# BatteryBalancer.net
KiCad netlist of a schematic drawn in EAGLE
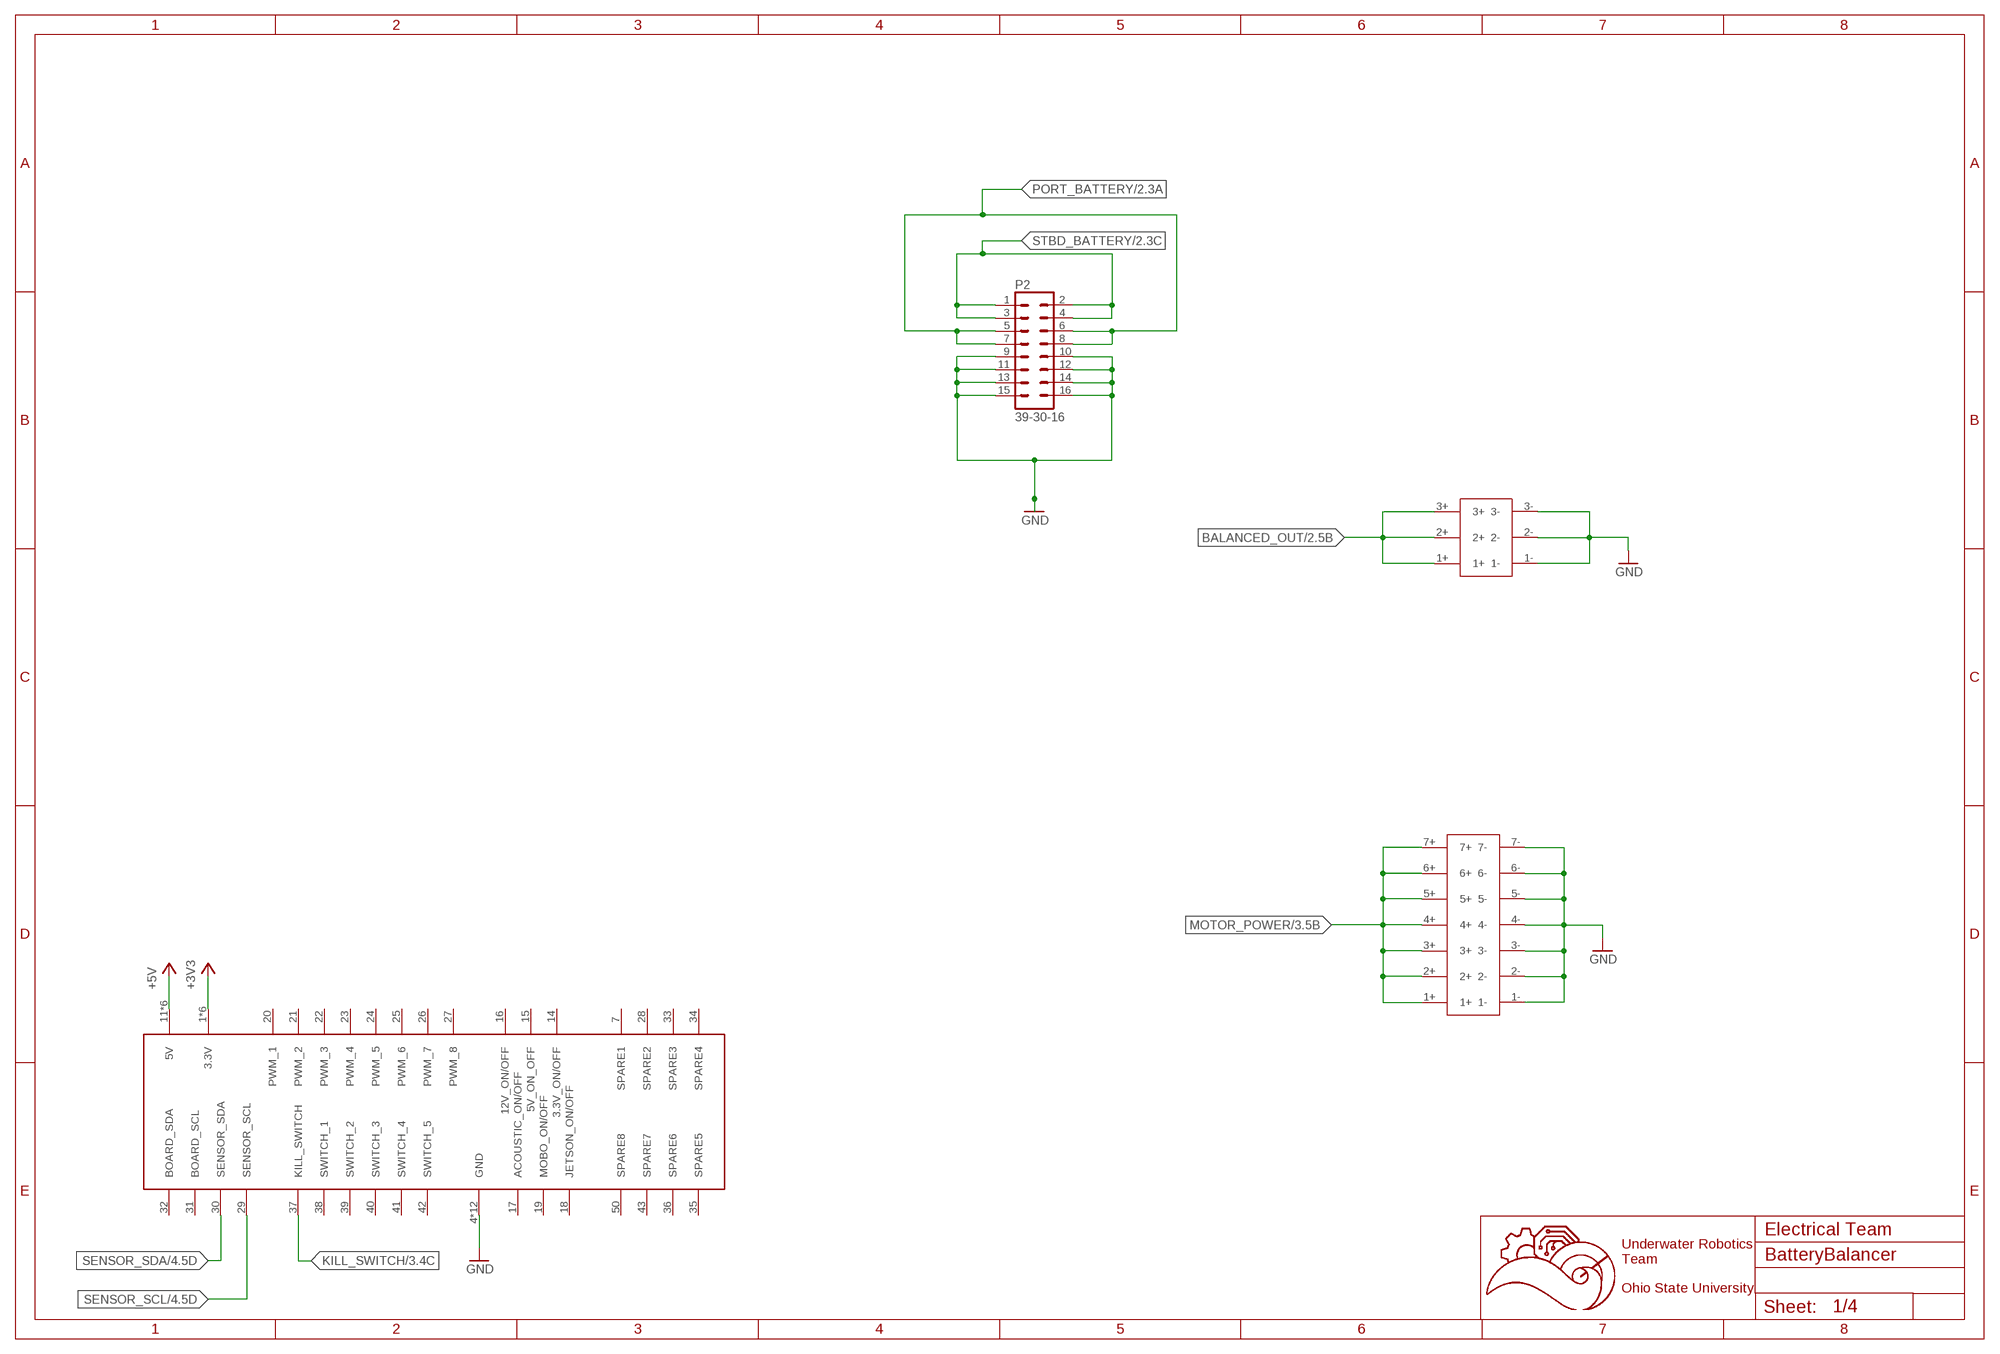
[diagram p0: schematic, sheet 1]
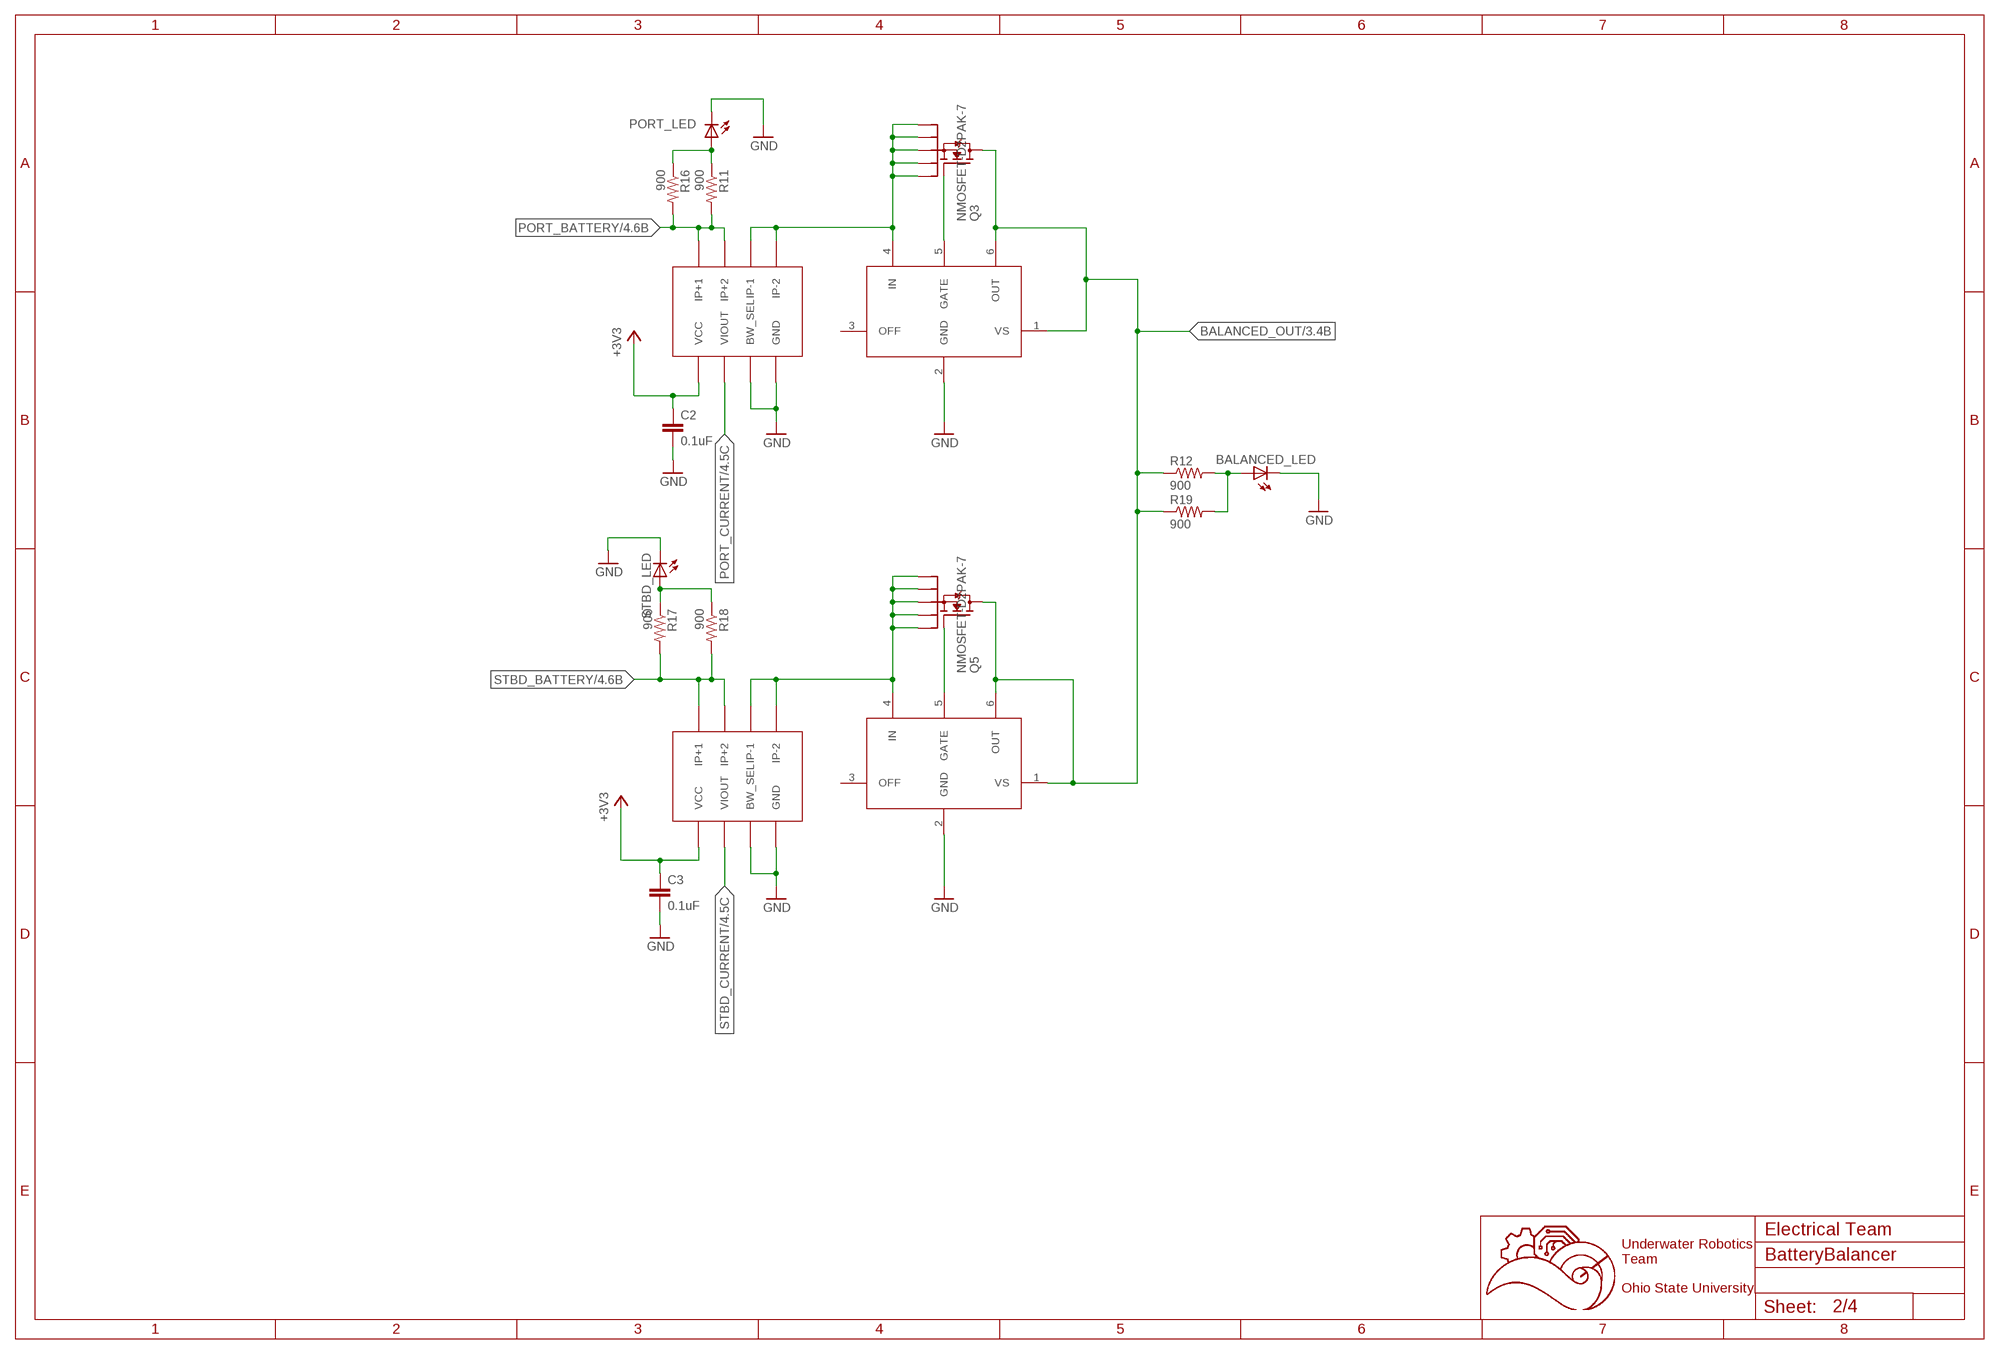
[diagram p1: schematic, sheet 2]
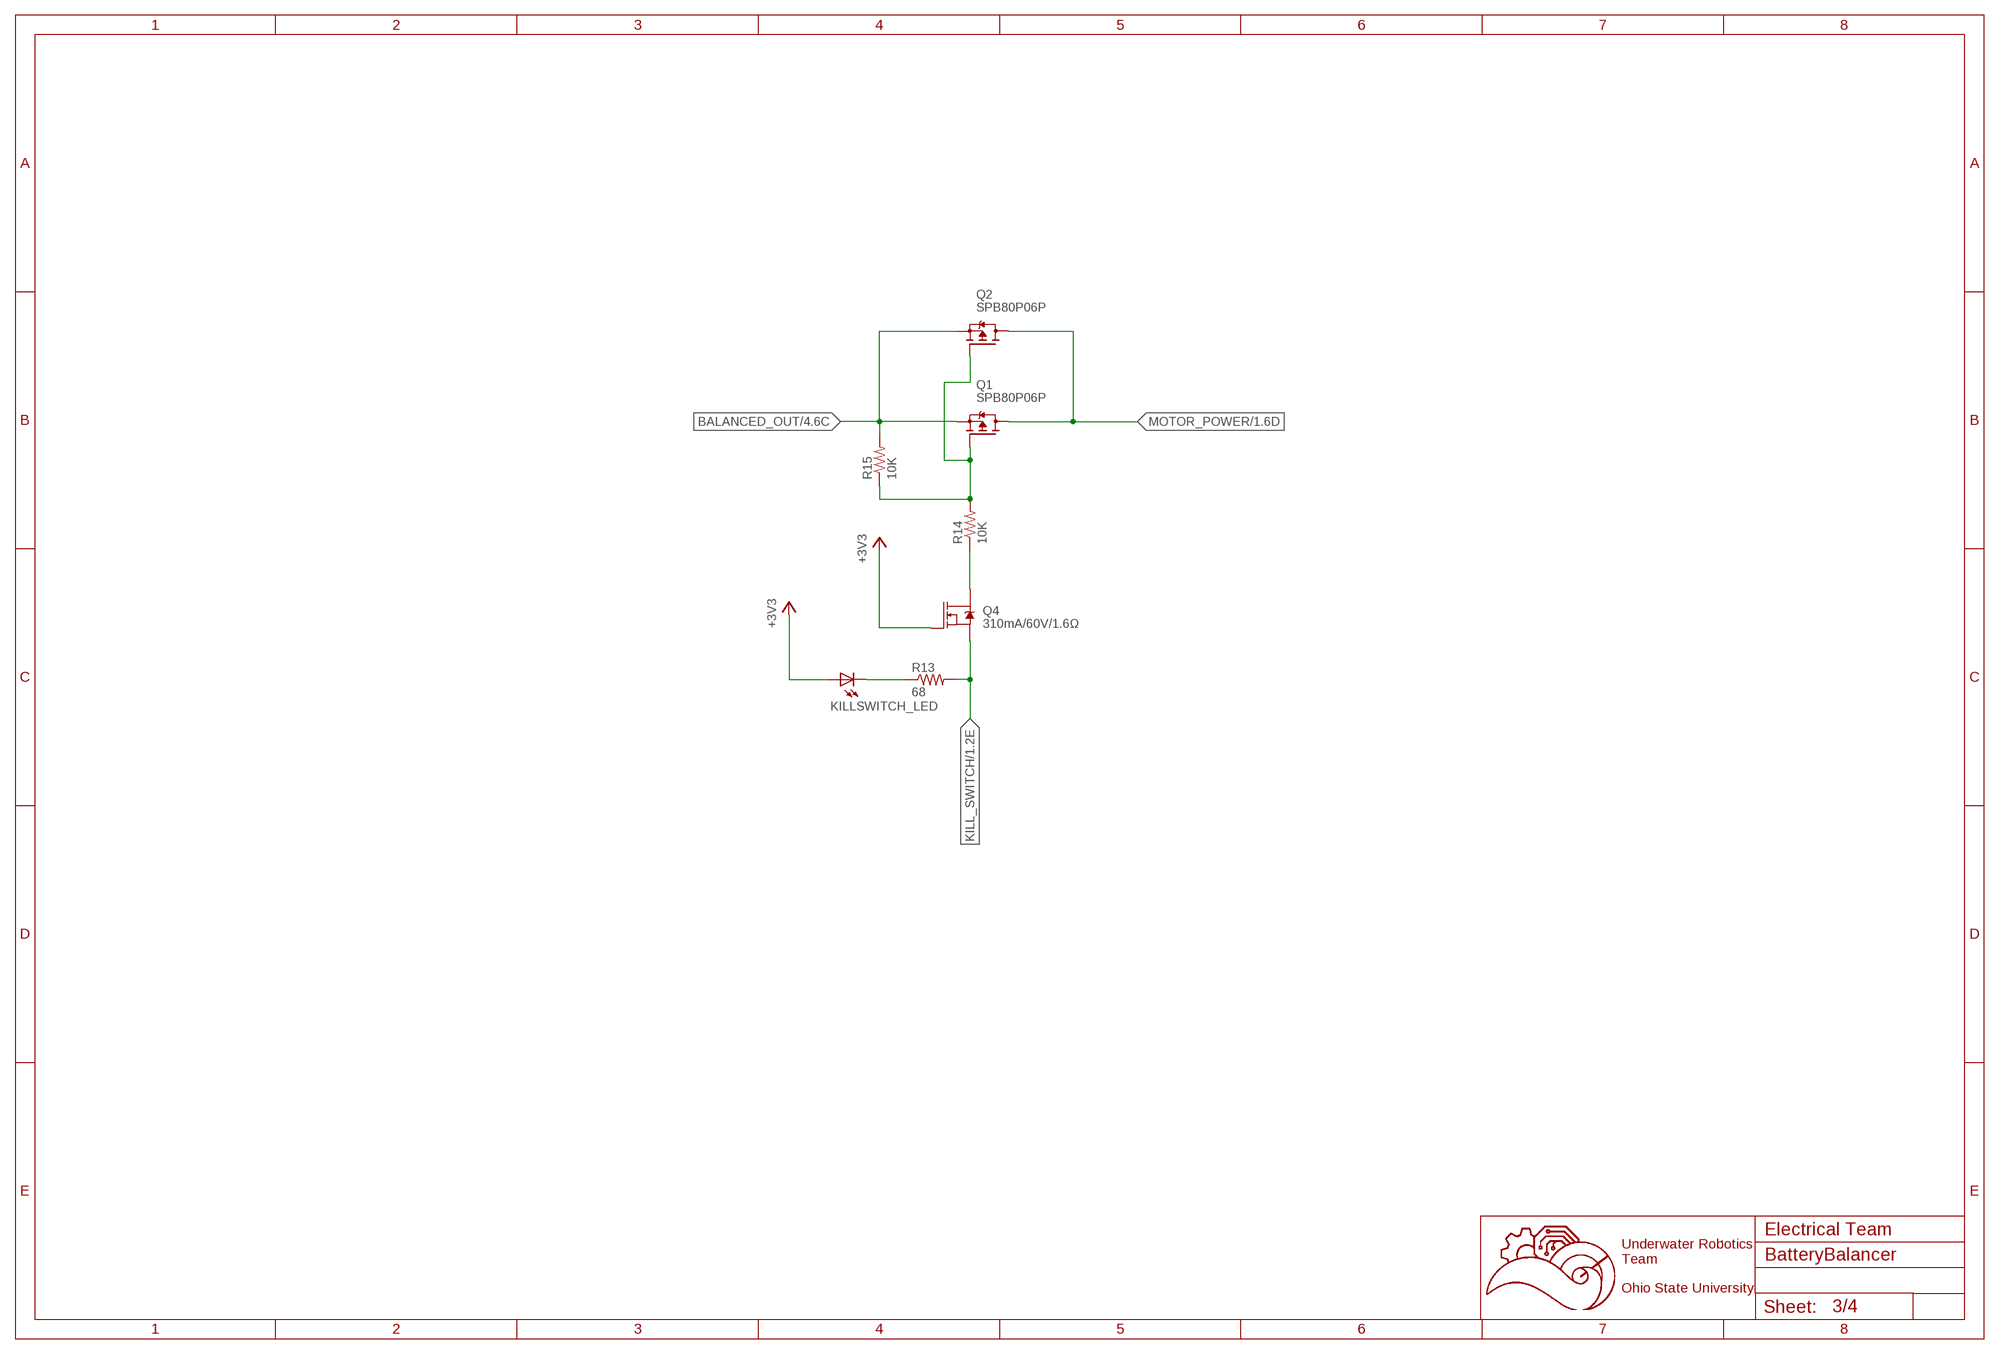
[diagram p2: schematic, sheet 3]
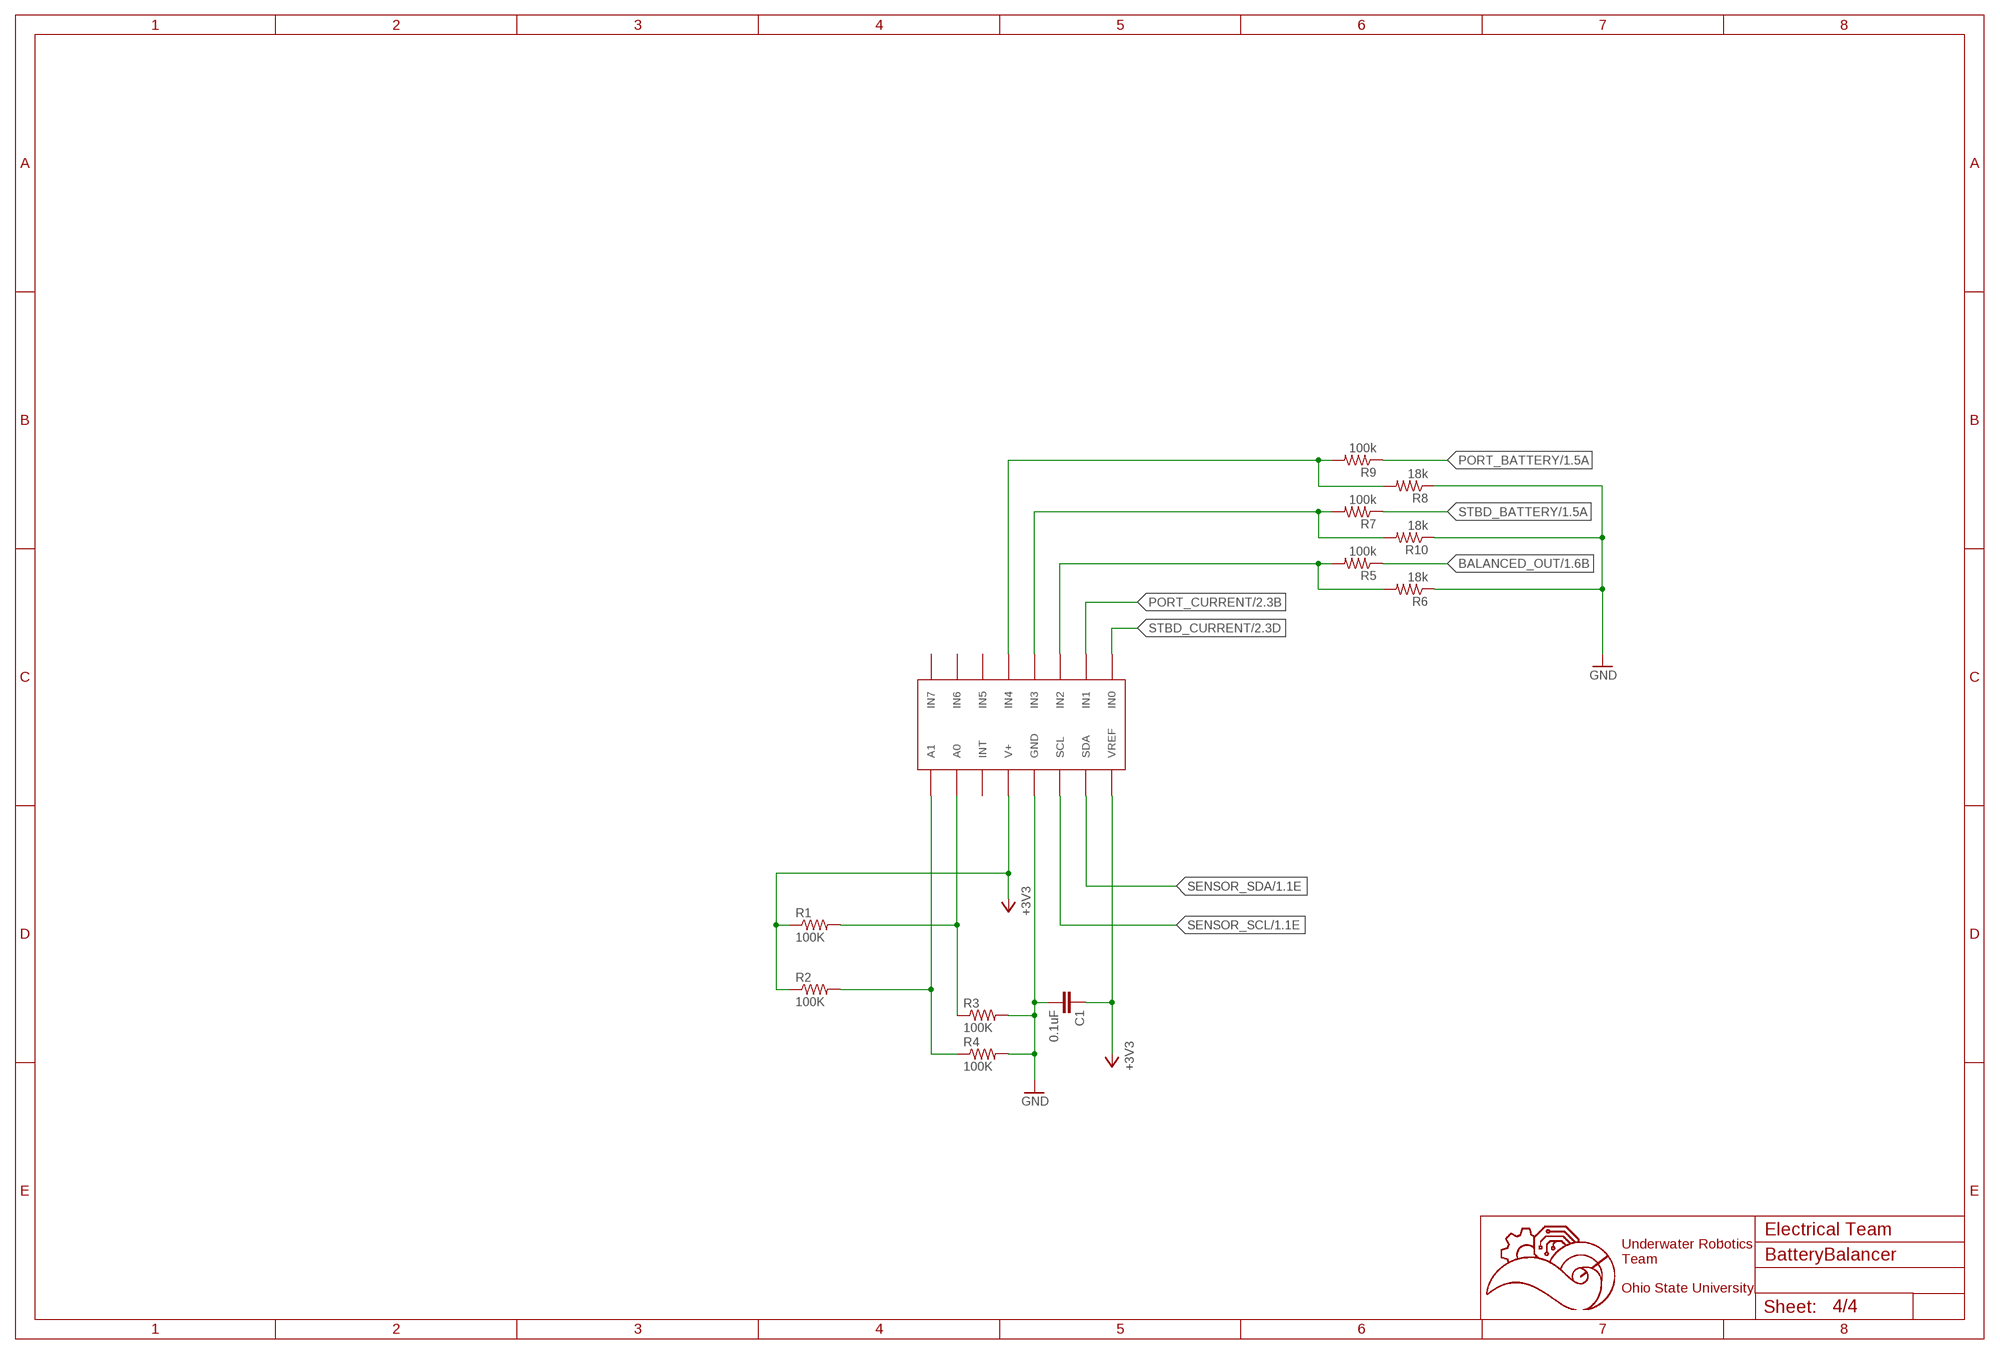
[diagram p3: schematic, sheet 4]

(export (version "E")
  (design (tool "Eeschema 10.0.6"))
  (components
    (comp (ref "C1")
      (value "0.1uF")
      (footprint "eagle-import:C0603")
      (libsource (lib "eagle-import") (part "C-EUC0603"))
    )
    (comp (ref "R1")
      (value "100K")
      (footprint "eagle-import:R0603")
      (libsource (lib "eagle-import") (part "R-US_R0603"))
    )
    (comp (ref "R2")
      (value "100K")
      (footprint "eagle-import:R0603")
      (libsource (lib "eagle-import") (part "R-US_R0603"))
    )
    (comp (ref "R3")
      (value "100K")
      (footprint "eagle-import:R0603")
      (libsource (lib "eagle-import") (part "R-US_R0603"))
    )
    (comp (ref "R4")
      (value "100K")
      (footprint "eagle-import:R0603")
      (libsource (lib "eagle-import") (part "R-US_R0603"))
    )
    (comp (ref "R5")
      (value "100k")
      (footprint "eagle-import:R0603")
      (libsource (lib "eagle-import") (part "R-US_R0603"))
    )
    (comp (ref "R6")
      (value "18k")
      (footprint "eagle-import:R0603")
      (libsource (lib "eagle-import") (part "R-US_R0603"))
    )
    (comp (ref "R7")
      (value "100k")
      (footprint "eagle-import:R0603")
      (libsource (lib "eagle-import") (part "R-US_R0603"))
    )
    (comp (ref "R8")
      (value "18k")
      (footprint "eagle-import:R0603")
      (libsource (lib "eagle-import") (part "R-US_R0603"))
    )
    (comp (ref "R9")
      (value "100k")
      (footprint "eagle-import:R0603")
      (libsource (lib "eagle-import") (part "R-US_R0603"))
    )
    (comp (ref "R10")
      (value "18k")
      (footprint "eagle-import:R0603")
      (libsource (lib "eagle-import") (part "R-US_R0603"))
    )
    (comp (ref "U$12")
      (value "ADC128D818")
      (footprint "eagle-import:TSSOP-16")
      (libsource (lib "eagle-import") (part "ADC128D818"))
    )
    (comp (ref "BALANCED_LED")
      (value "LEDCHIP-LED0603")
      (footprint "eagle-import:CHIP-LED0603")
      (libsource (lib "eagle-import") (part "LEDCHIP-LED0603"))
    )
    (comp (ref "C2")
      (value "0.1uF")
      (footprint "eagle-import:C0603")
      (libsource (lib "eagle-import") (part "C-EUC0603"))
    )
    (comp (ref "C3")
      (value "0.1uF")
      (footprint "eagle-import:C0603")
      (libsource (lib "eagle-import") (part "C-EUC0603"))
    )
    (comp (ref "PORT_LED")
      (value "LEDCHIP-LED0603")
      (footprint "eagle-import:CHIP-LED0603")
      (libsource (lib "eagle-import") (part "LEDCHIP-LED0603"))
    )
    (comp (ref "Q3")
      (value "NMOSFET-D2PAK-7")
      (footprint "eagle-import:D2PAK-7")
      (libsource (lib "eagle-import") (part "NMOSFET-D2PAK-7"))
    )
    (comp (ref "Q5")
      (value "NMOSFET-D2PAK-7")
      (footprint "eagle-import:D2PAK-7")
      (libsource (lib "eagle-import") (part "NMOSFET-D2PAK-7"))
    )
    (comp (ref "R11")
      (value "900")
      (footprint "eagle-import:R0603")
      (libsource (lib "eagle-import") (part "R-US_R0603"))
    )
    (comp (ref "R12")
      (value "900")
      (footprint "eagle-import:R0603")
      (libsource (lib "eagle-import") (part "R-US_R0603"))
    )
    (comp (ref "R16")
      (value "900")
      (footprint "eagle-import:R0603")
      (libsource (lib "eagle-import") (part "R-US_R0603"))
    )
    (comp (ref "R17")
      (value "900")
      (footprint "eagle-import:R0603")
      (libsource (lib "eagle-import") (part "R-US_R0603"))
    )
    (comp (ref "R18")
      (value "900")
      (footprint "eagle-import:R0603")
      (libsource (lib "eagle-import") (part "R-US_R0603"))
    )
    (comp (ref "R19")
      (value "900")
      (footprint "eagle-import:R0603")
      (libsource (lib "eagle-import") (part "R-US_R0603"))
    )
    (comp (ref "STBD_LED")
      (value "LEDCHIP-LED0603")
      (footprint "eagle-import:CHIP-LED0603")
      (libsource (lib "eagle-import") (part "LEDCHIP-LED0603"))
    )
    (comp (ref "U$2")
      (value "LM5050")
      (footprint "eagle-import:LM5050")
      (libsource (lib "eagle-import") (part "LM5050"))
    )
    (comp (ref "U$3")
      (value "LM5050")
      (footprint "eagle-import:LM5050")
      (libsource (lib "eagle-import") (part "LM5050"))
    )
    (comp (ref "U$6")
      (value "ACS722")
      (footprint "eagle-import:SOIC-8")
      (libsource (lib "eagle-import") (part "ACS722"))
    )
    (comp (ref "U$7")
      (value "ACS722")
      (footprint "eagle-import:SOIC-8")
      (libsource (lib "eagle-import") (part "ACS722"))
    )
    (comp (ref "P2")
      (value "39-30-16")
      (footprint "eagle-import:39-30-_16_")
      (libsource (lib "eagle-import") (part "39-30-?16?"))
    )
    (comp (ref "U$1")
      (value "5530843-EDGE")
      (footprint "eagle-import:5530843-6-BOARDFINGERS")
      (libsource (lib "eagle-import") (part "5530843-EDGE"))
    )
    (comp (ref "U$4")
      (value "14PIN-VERT")
      (footprint "eagle-import:14PIN_VERT")
      (libsource (lib "eagle-import") (part "14PIN-VERT"))
    )
    (comp (ref "U$13")
      (value "6PIN-VERT")
      (footprint "eagle-import:6PIN_VERT")
      (libsource (lib "eagle-import") (part "6PIN-VERT"))
    )
    (comp (ref "KILLSWITCH_LED")
      (value "LEDCHIP-LED0603")
      (footprint "eagle-import:CHIP-LED0603")
      (libsource (lib "eagle-import") (part "LEDCHIP-LED0603"))
    )
    (comp (ref "Q1")
      (value "SPB80P06P")
      (footprint "eagle-import:TO263")
      (libsource (lib "eagle-import") (part "SPB80P06P"))
    )
    (comp (ref "Q2")
      (value "SPB80P06P")
      (footprint "eagle-import:TO263")
      (libsource (lib "eagle-import") (part "SPB80P06P"))
    )
    (comp (ref "Q4")
      (value "310mA/60V/1.6Ω")
      (footprint "eagle-import:SOT323")
      (libsource (lib "eagle-import") (part "MOSFET-NCH-2N7002PW"))
    )
    (comp (ref "R13")
      (value "68")
      (footprint "eagle-import:R0603")
      (libsource (lib "eagle-import") (part "R-US_R0603"))
    )
    (comp (ref "R14")
      (value "10K")
      (footprint "eagle-import:R0603")
      (libsource (lib "eagle-import") (part "R-US_R0603"))
    )
    (comp (ref "R15")
      (value "10K")
      (footprint "eagle-import:R0603")
      (libsource (lib "eagle-import") (part "R-US_R0603"))
    )
  )
  (nets
    (net (code "1") (name "+3V3") (class "Default")
      (node (ref "C1") (pin "1") (pinfunction "1_1") (pintype "passive"))
      (node (ref "C2") (pin "1") (pinfunction "1_1") (pintype "passive"))
      (node (ref "C3") (pin "1") (pinfunction "1_1") (pintype "passive"))
      (node (ref "KILLSWITCH_LED") (pin "A") (pinfunction "A_A") (pintype "passive"))
      (node (ref "Q4") (pin "1") (pinfunction "G_1") (pintype "bidirectional"))
      (node (ref "R1") (pin "1") (pinfunction "1_1") (pintype "passive"))
      (node (ref "R2") (pin "1") (pinfunction "1_1") (pintype "passive"))
      (node (ref "U$1") (pin "1") (pinfunction "3.3V_1") (pintype "bidirectional"))
      (node (ref "U$1") (pin "2") (pinfunction "3.3V_2") (pintype "bidirectional"))
      (node (ref "U$1") (pin "3") (pinfunction "3.3V_3") (pintype "bidirectional"))
      (node (ref "U$1") (pin "54") (pinfunction "3.3V_54") (pintype "bidirectional"))
      (node (ref "U$1") (pin "55") (pinfunction "3.3V_55") (pintype "bidirectional"))
      (node (ref "U$1") (pin "56") (pinfunction "3.3V_56") (pintype "bidirectional"))
      (node (ref "U$12") (pin "V+") (pinfunction "V+_V+") (pintype "bidirectional"))
      (node (ref "U$12") (pin "VREF") (pinfunction "VREF_VREF") (pintype "bidirectional"))
      (node (ref "U$6") (pin "VCC") (pinfunction "VCC_VCC") (pintype "bidirectional"))
      (node (ref "U$7") (pin "VCC") (pinfunction "VCC_VCC") (pintype "bidirectional"))
    )
    (net (code "2") (name "+5V") (class "Default")
      (node (ref "U$1") (pin "11") (pinfunction "5V_11") (pintype "bidirectional"))
      (node (ref "U$1") (pin "12") (pinfunction "5V_12") (pintype "bidirectional"))
      (node (ref "U$1") (pin "13") (pinfunction "5V_13") (pintype "bidirectional"))
      (node (ref "U$1") (pin "44") (pinfunction "5V_44") (pintype "bidirectional"))
      (node (ref "U$1") (pin "45") (pinfunction "5V_45") (pintype "bidirectional"))
      (node (ref "U$1") (pin "46") (pinfunction "5V_46") (pintype "bidirectional"))
    )
    (net (code "3") (name "BALANCED_OUT") (class "Default")
      (node (ref "Q1") (pin "2") (pinfunction "S_2") (pintype "passive"))
      (node (ref "Q2") (pin "2") (pinfunction "S_2") (pintype "passive"))
      (node (ref "Q3") (pin "D") (pinfunction "D_D") (pintype "passive"))
      (node (ref "Q5") (pin "D") (pinfunction "D_D") (pintype "passive"))
      (node (ref "R12") (pin "1") (pinfunction "1_1") (pintype "passive"))
      (node (ref "R15") (pin "2") (pinfunction "2_2") (pintype "passive"))
      (node (ref "R19") (pin "1") (pinfunction "1_1") (pintype "passive"))
      (node (ref "R5") (pin "1") (pinfunction "1_1") (pintype "passive"))
      (node (ref "U$13") (pin "1+") (pinfunction "1+_1+") (pintype "bidirectional"))
      (node (ref "U$13") (pin "2+") (pinfunction "2+_2+") (pintype "bidirectional"))
      (node (ref "U$13") (pin "3+") (pinfunction "3+_3+") (pintype "bidirectional"))
      (node (ref "U$2") (pin "1") (pinfunction "VS_1") (pintype "bidirectional"))
      (node (ref "U$2") (pin "6") (pinfunction "OUT_6") (pintype "bidirectional"))
      (node (ref "U$3") (pin "1") (pinfunction "VS_1") (pintype "bidirectional"))
      (node (ref "U$3") (pin "6") (pinfunction "OUT_6") (pintype "bidirectional"))
    )
    (net (code "4") (name "GND") (class "Default")
      (node (ref "BALANCED_LED") (pin "C") (pinfunction "C_C") (pintype "passive"))
      (node (ref "C1") (pin "2") (pinfunction "2_2") (pintype "passive"))
      (node (ref "C2") (pin "2") (pinfunction "2_2") (pintype "passive"))
      (node (ref "C3") (pin "2") (pinfunction "2_2") (pintype "passive"))
      (node (ref "P2") (pin "10") (pinfunction "10_10") (pintype "passive"))
      (node (ref "P2") (pin "11") (pinfunction "11_11") (pintype "passive"))
      (node (ref "P2") (pin "12") (pinfunction "12_12") (pintype "passive"))
      (node (ref "P2") (pin "13") (pinfunction "13_13") (pintype "passive"))
      (node (ref "P2") (pin "14") (pinfunction "14_14") (pintype "passive"))
      (node (ref "P2") (pin "15") (pinfunction "15_15") (pintype "passive"))
      (node (ref "P2") (pin "16") (pinfunction "16_16") (pintype "passive"))
      (node (ref "P2") (pin "9") (pinfunction "9_9") (pintype "passive"))
      (node (ref "PORT_LED") (pin "C") (pinfunction "C_C") (pintype "passive"))
      (node (ref "R10") (pin "1") (pinfunction "1_1") (pintype "passive"))
      (node (ref "R3") (pin "2") (pinfunction "2_2") (pintype "passive"))
      (node (ref "R4") (pin "2") (pinfunction "2_2") (pintype "passive"))
      (node (ref "R6") (pin "1") (pinfunction "1_1") (pintype "passive"))
      (node (ref "R8") (pin "1") (pinfunction "1_1") (pintype "passive"))
      (node (ref "STBD_LED") (pin "C") (pinfunction "C_C") (pintype "passive"))
      (node (ref "U$1") (pin "10") (pinfunction "GND_10") (pintype "bidirectional"))
      (node (ref "U$1") (pin "4") (pinfunction "GND_4") (pintype "bidirectional"))
      (node (ref "U$1") (pin "47") (pinfunction "GND_47") (pintype "bidirectional"))
      (node (ref "U$1") (pin "48") (pinfunction "GND_48") (pintype "bidirectional"))
      (node (ref "U$1") (pin "49") (pinfunction "GND_49") (pintype "bidirectional"))
      (node (ref "U$1") (pin "5") (pinfunction "GND_5") (pintype "bidirectional"))
      (node (ref "U$1") (pin "51") (pinfunction "GND_51") (pintype "bidirectional"))
      (node (ref "U$1") (pin "52") (pinfunction "GND_52") (pintype "bidirectional"))
      (node (ref "U$1") (pin "53") (pinfunction "GND_53") (pintype "bidirectional"))
      (node (ref "U$1") (pin "6") (pinfunction "GND_6") (pintype "bidirectional"))
      (node (ref "U$1") (pin "8") (pinfunction "GND_8") (pintype "bidirectional"))
      (node (ref "U$1") (pin "9") (pinfunction "GND_9") (pintype "bidirectional"))
      (node (ref "U$12") (pin "GND") (pinfunction "GND_GND") (pintype "bidirectional"))
      (node (ref "U$13") (pin "1-") (pinfunction "1-_1-") (pintype "bidirectional"))
      (node (ref "U$13") (pin "2-") (pinfunction "2-_2-") (pintype "bidirectional"))
      (node (ref "U$13") (pin "3-") (pinfunction "3-_3-") (pintype "bidirectional"))
      (node (ref "U$2") (pin "2") (pinfunction "GND_2") (pintype "bidirectional"))
      (node (ref "U$3") (pin "2") (pinfunction "GND_2") (pintype "bidirectional"))
      (node (ref "U$4") (pin "1-") (pinfunction "1-_1-") (pintype "bidirectional"))
      (node (ref "U$4") (pin "2-") (pinfunction "2-_2-") (pintype "bidirectional"))
      (node (ref "U$4") (pin "3-") (pinfunction "3-_3-") (pintype "bidirectional"))
      (node (ref "U$4") (pin "4-") (pinfunction "4-_4-") (pintype "bidirectional"))
      (node (ref "U$4") (pin "5-") (pinfunction "5-_5-") (pintype "bidirectional"))
      (node (ref "U$4") (pin "6-") (pinfunction "6-_6-") (pintype "bidirectional"))
      (node (ref "U$4") (pin "7-") (pinfunction "7-_7-") (pintype "bidirectional"))
      (node (ref "U$6") (pin "BW_SEL") (pinfunction "BW_SEL_BW_SEL") (pintype "bidirectional"))
      (node (ref "U$6") (pin "GND") (pinfunction "GND_GND") (pintype "bidirectional"))
      (node (ref "U$7") (pin "BW_SEL") (pinfunction "BW_SEL_BW_SEL") (pintype "bidirectional"))
      (node (ref "U$7") (pin "GND") (pinfunction "GND_GND") (pintype "bidirectional"))
    )
    (net (code "5") (name "KILL_SWITCH") (class "Default")
      (node (ref "Q4") (pin "2") (pinfunction "S_2") (pintype "bidirectional"))
      (node (ref "R13") (pin "2") (pinfunction "2_2") (pintype "passive"))
      (node (ref "U$1") (pin "37") (pinfunction "KILL_SWITCH_37") (pintype "output"))
    )
    (net (code "6") (name "MOTOR_POWER") (class "Default")
      (node (ref "Q1") (pin "3") (pinfunction "D_3") (pintype "passive"))
      (node (ref "Q2") (pin "3") (pinfunction "D_3") (pintype "passive"))
      (node (ref "U$4") (pin "1+") (pinfunction "1+_1+") (pintype "bidirectional"))
      (node (ref "U$4") (pin "2+") (pinfunction "2+_2+") (pintype "bidirectional"))
      (node (ref "U$4") (pin "3+") (pinfunction "3+_3+") (pintype "bidirectional"))
      (node (ref "U$4") (pin "4+") (pinfunction "4+_4+") (pintype "bidirectional"))
      (node (ref "U$4") (pin "5+") (pinfunction "5+_5+") (pintype "bidirectional"))
      (node (ref "U$4") (pin "6+") (pinfunction "6+_6+") (pintype "bidirectional"))
      (node (ref "U$4") (pin "7+") (pinfunction "7+_7+") (pintype "bidirectional"))
    )
    (net (code "7") (name "Net-(BALANCED_LED-PadA)") (class "Default")
      (node (ref "BALANCED_LED") (pin "A") (pinfunction "A_A") (pintype "passive"))
      (node (ref "R12") (pin "2") (pinfunction "2_2") (pintype "passive"))
      (node (ref "R19") (pin "2") (pinfunction "2_2") (pintype "passive"))
    )
    (net (code "8") (name "Net-(KILLSWITCH_LED-PadC)") (class "Default")
      (node (ref "KILLSWITCH_LED") (pin "C") (pinfunction "C_C") (pintype "passive"))
      (node (ref "R13") (pin "1") (pinfunction "1_1") (pintype "passive"))
    )
    (net (code "9") (name "Net-(PORT_LED-PadA)") (class "Default")
      (node (ref "PORT_LED") (pin "A") (pinfunction "A_A") (pintype "passive"))
      (node (ref "R11") (pin "1") (pinfunction "1_1") (pintype "passive"))
      (node (ref "R16") (pin "1") (pinfunction "1_1") (pintype "passive"))
    )
    (net (code "10") (name "Net-(Q1-G)") (class "Default")
      (node (ref "Q1") (pin "1") (pinfunction "G_1") (pintype "passive"))
      (node (ref "Q2") (pin "1") (pinfunction "G_1") (pintype "passive"))
      (node (ref "R14") (pin "2") (pinfunction "2_2") (pintype "passive"))
      (node (ref "R15") (pin "1") (pinfunction "1_1") (pintype "passive"))
    )
    (net (code "11") (name "Net-(Q4-D)") (class "Default")
      (node (ref "Q4") (pin "3") (pinfunction "D_3") (pintype "bidirectional"))
      (node (ref "R14") (pin "1") (pinfunction "1_1") (pintype "passive"))
    )
    (net (code "12") (name "Net-(R1-Pad2)") (class "Default")
      (node (ref "R1") (pin "2") (pinfunction "2_2") (pintype "passive"))
      (node (ref "R3") (pin "1") (pinfunction "1_1") (pintype "passive"))
      (node (ref "U$12") (pin "A0") (pinfunction "A0_A0") (pintype "bidirectional"))
    )
    (net (code "13") (name "Net-(R2-Pad2)") (class "Default")
      (node (ref "R2") (pin "2") (pinfunction "2_2") (pintype "passive"))
      (node (ref "R4") (pin "1") (pinfunction "1_1") (pintype "passive"))
      (node (ref "U$12") (pin "A1") (pinfunction "A1_A1") (pintype "bidirectional"))
    )
    (net (code "14") (name "Net-(R5-Pad2)") (class "Default")
      (node (ref "R5") (pin "2") (pinfunction "2_2") (pintype "passive"))
      (node (ref "R6") (pin "2") (pinfunction "2_2") (pintype "passive"))
      (node (ref "U$12") (pin "IN2") (pinfunction "IN2_IN2") (pintype "bidirectional"))
    )
    (net (code "15") (name "Net-(R8-Pad2)") (class "Default")
      (node (ref "R8") (pin "2") (pinfunction "2_2") (pintype "passive"))
      (node (ref "R9") (pin "2") (pinfunction "2_2") (pintype "passive"))
      (node (ref "U$12") (pin "IN4") (pinfunction "IN4_IN4") (pintype "bidirectional"))
    )
    (net (code "16") (name "Net-(R10-Pad2)") (class "Default")
      (node (ref "R10") (pin "2") (pinfunction "2_2") (pintype "passive"))
      (node (ref "R7") (pin "2") (pinfunction "2_2") (pintype "passive"))
      (node (ref "U$12") (pin "IN3") (pinfunction "IN3_IN3") (pintype "bidirectional"))
    )
    (net (code "17") (name "Net-(R17-Pad1)") (class "Default")
      (node (ref "R17") (pin "1") (pinfunction "1_1") (pintype "passive"))
      (node (ref "R18") (pin "1") (pinfunction "1_1") (pintype "passive"))
      (node (ref "STBD_LED") (pin "A") (pinfunction "A_A") (pintype "passive"))
    )
    (net (code "18") (name "Net-(U$2-GATE)") (class "Default")
      (node (ref "Q3") (pin "G") (pinfunction "G_G") (pintype "passive"))
      (node (ref "U$2") (pin "5") (pinfunction "GATE_5") (pintype "bidirectional"))
    )
    (net (code "19") (name "Net-(U$2-IN)") (class "Default")
      (node (ref "Q3") (pin "S1") (pinfunction "S1_S1") (pintype "passive"))
      (node (ref "Q3") (pin "S2") (pinfunction "S2_S2") (pintype "passive"))
      (node (ref "Q3") (pin "S3") (pinfunction "S3_S3") (pintype "passive"))
      (node (ref "Q3") (pin "S4") (pinfunction "S4_S4") (pintype "passive"))
      (node (ref "Q3") (pin "S5") (pinfunction "S5_S5") (pintype "passive"))
      (node (ref "U$2") (pin "4") (pinfunction "IN_4") (pintype "bidirectional"))
      (node (ref "U$6") (pin "IP-1") (pinfunction "IP-1_IP-1") (pintype "bidirectional"))
      (node (ref "U$6") (pin "IP-2") (pinfunction "IP-2_IP-2") (pintype "bidirectional"))
    )
    (net (code "20") (name "Net-(U$3-GATE)") (class "Default")
      (node (ref "Q5") (pin "G") (pinfunction "G_G") (pintype "passive"))
      (node (ref "U$3") (pin "5") (pinfunction "GATE_5") (pintype "bidirectional"))
    )
    (net (code "21") (name "Net-(U$3-IN)") (class "Default")
      (node (ref "Q5") (pin "S1") (pinfunction "S1_S1") (pintype "passive"))
      (node (ref "Q5") (pin "S2") (pinfunction "S2_S2") (pintype "passive"))
      (node (ref "Q5") (pin "S3") (pinfunction "S3_S3") (pintype "passive"))
      (node (ref "Q5") (pin "S4") (pinfunction "S4_S4") (pintype "passive"))
      (node (ref "Q5") (pin "S5") (pinfunction "S5_S5") (pintype "passive"))
      (node (ref "U$3") (pin "4") (pinfunction "IN_4") (pintype "bidirectional"))
      (node (ref "U$7") (pin "IP-1") (pinfunction "IP-1_IP-1") (pintype "bidirectional"))
      (node (ref "U$7") (pin "IP-2") (pinfunction "IP-2_IP-2") (pintype "bidirectional"))
    )
    (net (code "22") (name "PORT_BATTERY") (class "Default")
      (node (ref "P2") (pin "5") (pinfunction "5_5") (pintype "passive"))
      (node (ref "P2") (pin "6") (pinfunction "6_6") (pintype "passive"))
      (node (ref "P2") (pin "7") (pinfunction "7_7") (pintype "passive"))
      (node (ref "P2") (pin "8") (pinfunction "8_8") (pintype "passive"))
      (node (ref "R11") (pin "2") (pinfunction "2_2") (pintype "passive"))
      (node (ref "R16") (pin "2") (pinfunction "2_2") (pintype "passive"))
      (node (ref "R9") (pin "1") (pinfunction "1_1") (pintype "passive"))
      (node (ref "U$6") (pin "IP+1") (pinfunction "IP+1_IP+1") (pintype "bidirectional"))
      (node (ref "U$6") (pin "IP+2") (pinfunction "IP+2_IP+2") (pintype "bidirectional"))
    )
    (net (code "23") (name "PORT_CURRENT") (class "Default")
      (node (ref "U$12") (pin "IN1") (pinfunction "IN1_IN1") (pintype "bidirectional"))
      (node (ref "U$6") (pin "VIOUT") (pinfunction "VIOUT_VIOUT") (pintype "bidirectional"))
    )
    (net (code "24") (name "SENSOR_SCL") (class "Default")
      (node (ref "U$1") (pin "29") (pinfunction "SENSOR_SCL_29") (pintype "bidirectional"))
      (node (ref "U$12") (pin "SCL") (pinfunction "SCL_SCL") (pintype "bidirectional"))
    )
    (net (code "25") (name "SENSOR_SDA") (class "Default")
      (node (ref "U$1") (pin "30") (pinfunction "SENSOR_SDA_30") (pintype "bidirectional"))
      (node (ref "U$12") (pin "SDA") (pinfunction "SDA_SDA") (pintype "bidirectional"))
    )
    (net (code "26") (name "STBD_BATTERY") (class "Default")
      (node (ref "P2") (pin "1") (pinfunction "1_1") (pintype "passive"))
      (node (ref "P2") (pin "2") (pinfunction "2_2") (pintype "passive"))
      (node (ref "P2") (pin "3") (pinfunction "3_3") (pintype "passive"))
      (node (ref "P2") (pin "4") (pinfunction "4_4") (pintype "passive"))
      (node (ref "R17") (pin "2") (pinfunction "2_2") (pintype "passive"))
      (node (ref "R18") (pin "2") (pinfunction "2_2") (pintype "passive"))
      (node (ref "R7") (pin "1") (pinfunction "1_1") (pintype "passive"))
      (node (ref "U$7") (pin "IP+1") (pinfunction "IP+1_IP+1") (pintype "bidirectional"))
      (node (ref "U$7") (pin "IP+2") (pinfunction "IP+2_IP+2") (pintype "bidirectional"))
    )
    (net (code "27") (name "STBD_CURRENT") (class "Default")
      (node (ref "U$12") (pin "IN0") (pinfunction "IN0_IN0") (pintype "bidirectional"))
      (node (ref "U$7") (pin "VIOUT") (pinfunction "VIOUT_VIOUT") (pintype "bidirectional"))
    )
    (net (code "28") (name "unconnected-(U$1-3.3V_ON{slash}OFF-Pad14)") (class "Default")
      (node (ref "U$1") (pin "14") (pinfunction "3.3V_ON/OFF_14") (pintype "bidirectional"))
    )
    (net (code "29") (name "unconnected-(U$1-5V_ON_OFF-Pad15)") (class "Default")
      (node (ref "U$1") (pin "15") (pinfunction "5V_ON_OFF_15") (pintype "bidirectional"))
    )
    (net (code "30") (name "unconnected-(U$1-12V_ON{slash}OFF-Pad16)") (class "Default")
      (node (ref "U$1") (pin "16") (pinfunction "12V_ON/OFF_16") (pintype "bidirectional"))
    )
    (net (code "31") (name "unconnected-(U$1-ACOUSTIC_ON{slash}OFF-Pad17)") (class "Default")
      (node (ref "U$1") (pin "17") (pinfunction "ACOUSTIC_ON/OFF_17") (pintype "bidirectional"))
    )
    (net (code "32") (name "unconnected-(U$1-BOARD_SCL-Pad31)") (class "Default")
      (node (ref "U$1") (pin "31") (pinfunction "BOARD_SCL_31") (pintype "bidirectional"))
    )
    (net (code "33") (name "unconnected-(U$1-BOARD_SDA-Pad32)") (class "Default")
      (node (ref "U$1") (pin "32") (pinfunction "BOARD_SDA_32") (pintype "bidirectional"))
    )
    (net (code "34") (name "unconnected-(U$1-JETSON_ON{slash}OFF-Pad18)") (class "Default")
      (node (ref "U$1") (pin "18") (pinfunction "JETSON_ON/OFF_18") (pintype "bidirectional"))
    )
    (net (code "35") (name "unconnected-(U$1-MOBO_ON{slash}OFF-Pad19)") (class "Default")
      (node (ref "U$1") (pin "19") (pinfunction "MOBO_ON/OFF_19") (pintype "bidirectional"))
    )
    (net (code "36") (name "unconnected-(U$1-PWM_1-Pad20)") (class "Default")
      (node (ref "U$1") (pin "20") (pinfunction "PWM_1_20") (pintype "bidirectional"))
    )
    (net (code "37") (name "unconnected-(U$1-PWM_2-Pad21)") (class "Default")
      (node (ref "U$1") (pin "21") (pinfunction "PWM_2_21") (pintype "bidirectional"))
    )
    (net (code "38") (name "unconnected-(U$1-PWM_3-Pad22)") (class "Default")
      (node (ref "U$1") (pin "22") (pinfunction "PWM_3_22") (pintype "bidirectional"))
    )
    (net (code "39") (name "unconnected-(U$1-PWM_4-Pad23)") (class "Default")
      (node (ref "U$1") (pin "23") (pinfunction "PWM_4_23") (pintype "bidirectional"))
    )
    (net (code "40") (name "unconnected-(U$1-PWM_5-Pad24)") (class "Default")
      (node (ref "U$1") (pin "24") (pinfunction "PWM_5_24") (pintype "bidirectional"))
    )
    (net (code "41") (name "unconnected-(U$1-PWM_6-Pad25)") (class "Default")
      (node (ref "U$1") (pin "25") (pinfunction "PWM_6_25") (pintype "bidirectional"))
    )
    (net (code "42") (name "unconnected-(U$1-PWM_7-Pad26)") (class "Default")
      (node (ref "U$1") (pin "26") (pinfunction "PWM_7_26") (pintype "bidirectional"))
    )
    (net (code "43") (name "unconnected-(U$1-PWM_8-Pad27)") (class "Default")
      (node (ref "U$1") (pin "27") (pinfunction "PWM_8_27") (pintype "bidirectional"))
    )
    (net (code "44") (name "unconnected-(U$1-SPARE1-Pad7)") (class "Default")
      (node (ref "U$1") (pin "7") (pinfunction "SPARE1_7") (pintype "bidirectional"))
    )
    (net (code "45") (name "unconnected-(U$1-SPARE2-Pad28)") (class "Default")
      (node (ref "U$1") (pin "28") (pinfunction "SPARE2_28") (pintype "bidirectional"))
    )
    (net (code "46") (name "unconnected-(U$1-SPARE3-Pad33)") (class "Default")
      (node (ref "U$1") (pin "33") (pinfunction "SPARE3_33") (pintype "bidirectional"))
    )
    (net (code "47") (name "unconnected-(U$1-SPARE4-Pad34)") (class "Default")
      (node (ref "U$1") (pin "34") (pinfunction "SPARE4_34") (pintype "bidirectional"))
    )
    (net (code "48") (name "unconnected-(U$1-SPARE5-Pad35)") (class "Default")
      (node (ref "U$1") (pin "35") (pinfunction "SPARE5_35") (pintype "bidirectional"))
    )
    (net (code "49") (name "unconnected-(U$1-SPARE6-Pad36)") (class "Default")
      (node (ref "U$1") (pin "36") (pinfunction "SPARE6_36") (pintype "bidirectional"))
    )
    (net (code "50") (name "unconnected-(U$1-SPARE7-Pad43)") (class "Default")
      (node (ref "U$1") (pin "43") (pinfunction "SPARE7_43") (pintype "bidirectional"))
    )
    (net (code "51") (name "unconnected-(U$1-SPARE8-Pad50)") (class "Default")
      (node (ref "U$1") (pin "50") (pinfunction "SPARE8_50") (pintype "bidirectional"))
    )
    (net (code "52") (name "unconnected-(U$1-SWITCH_1-Pad38)") (class "Default")
      (node (ref "U$1") (pin "38") (pinfunction "SWITCH_1_38") (pintype "output"))
    )
    (net (code "53") (name "unconnected-(U$1-SWITCH_2-Pad39)") (class "Default")
      (node (ref "U$1") (pin "39") (pinfunction "SWITCH_2_39") (pintype "output"))
    )
    (net (code "54") (name "unconnected-(U$1-SWITCH_3-Pad40)") (class "Default")
      (node (ref "U$1") (pin "40") (pinfunction "SWITCH_3_40") (pintype "output"))
    )
    (net (code "55") (name "unconnected-(U$1-SWITCH_4-Pad41)") (class "Default")
      (node (ref "U$1") (pin "41") (pinfunction "SWITCH_4_41") (pintype "output"))
    )
    (net (code "56") (name "unconnected-(U$1-SWITCH_5-Pad42)") (class "Default")
      (node (ref "U$1") (pin "42") (pinfunction "SWITCH_5_42") (pintype "output"))
    )
    (net (code "57") (name "unconnected-(U$2-OFF-Pad3)") (class "Default")
      (node (ref "U$2") (pin "3") (pinfunction "OFF_3") (pintype "bidirectional"))
    )
    (net (code "58") (name "unconnected-(U$3-OFF-Pad3)") (class "Default")
      (node (ref "U$3") (pin "3") (pinfunction "OFF_3") (pintype "bidirectional"))
    )
    (net (code "59") (name "unconnected-(U$12-PadIN5)") (class "Default")
      (node (ref "U$12") (pin "IN5") (pinfunction "IN5_IN5") (pintype "bidirectional"))
    )
    (net (code "60") (name "unconnected-(U$12-PadIN6)") (class "Default")
      (node (ref "U$12") (pin "IN6") (pinfunction "IN6_IN6") (pintype "bidirectional"))
    )
    (net (code "61") (name "unconnected-(U$12-PadIN7)") (class "Default")
      (node (ref "U$12") (pin "IN7") (pinfunction "IN7_IN7") (pintype "bidirectional"))
    )
    (net (code "62") (name "unconnected-(U$12-PadINT)") (class "Default")
      (node (ref "U$12") (pin "INT") (pinfunction "INT_INT") (pintype "bidirectional"))
    )
  )
)
